# EEG_Front-End.net
KiCad netlist of a schematic drawn in Altium Designer
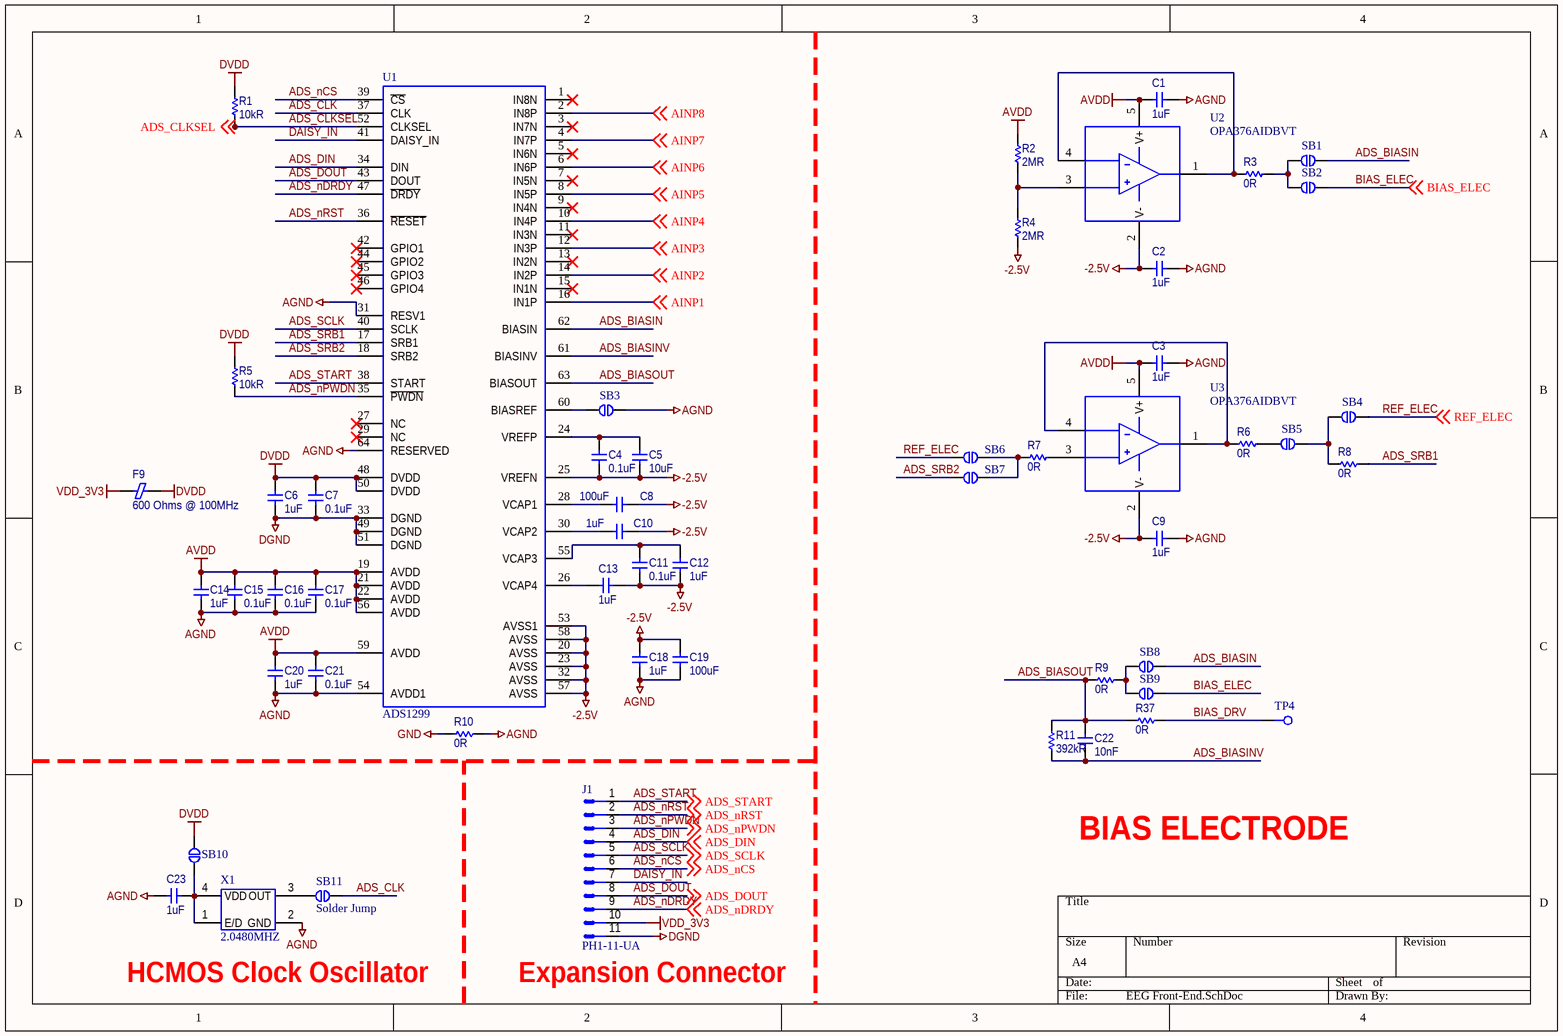
[diagram p0: EEG Front-End.SchDoc]

(export (version "E")
  (design (tool "Eeschema 10.0.6"))
  (components
    (comp (ref "C1")
      (value "1uF")
      (footprint "C1005X04N")
      (description "CAP CER,1UF,10%,16V,X5R,0402,SMD")
      (fields
        (field (name "MANUFACTURER PART NUMBER") "EMK105BJ105KV-F")
        (field (name "MANUFACTURER") "Taiyo Yuden")
      )
      (libsource (lib "Database Library") (part "C_CAPN"))
    )
    (comp (ref "C2")
      (value "1uF")
      (footprint "C1005X04N")
      (description "CAP CER,1UF,10%,16V,X5R,0402,SMD")
      (fields
        (field (name "MANUFACTURER PART NUMBER") "EMK105BJ105KV-F")
        (field (name "MANUFACTURER") "Taiyo Yuden")
      )
      (libsource (lib "Database Library") (part "C_CAPN"))
    )
    (comp (ref "C3")
      (value "1uF")
      (footprint "C1005X04N")
      (description "CAP CER,1UF,10%,16V,X5R,0402,SMD")
      (fields
        (field (name "MANUFACTURER PART NUMBER") "EMK105BJ105KV-F")
        (field (name "MANUFACTURER") "Taiyo Yuden")
      )
      (libsource (lib "Database Library") (part "C_CAPN"))
    )
    (comp (ref "C4")
      (value "0.1uF")
      (footprint "C1005X04N")
      (description "CAP CER,0.1UF,20%,25V,X5R,0402,SMD")
      (fields
        (field (name "MANUFACTURER PART NUMBER") "TMK105BJ104MV-F")
        (field (name "MANUFACTURER") "Taiyo Yuden")
      )
      (libsource (lib "Database Library") (part "C_CAPN"))
    )
    (comp (ref "C5")
      (value "10uF")
      (footprint "C1608X06N")
      (description "CAP CER,10UF,20%,10V,X5R,0603,SMD")
      (fields
        (field (name "MANUFACTURER PART NUMBER") "LMK107BBJ106MAHT")
        (field (name "MANUFACTURER") "Taiyo Yuden")
      )
      (libsource (lib "Database Library") (part "C_CAPN"))
    )
    (comp (ref "C6")
      (value "1uF")
      (footprint "C1005X04N")
      (description "CAP CER,1UF,10%,16V,X5R,0402,SMD")
      (fields
        (field (name "MANUFACTURER PART NUMBER") "EMK105BJ105KV-F")
        (field (name "MANUFACTURER") "Taiyo Yuden")
      )
      (libsource (lib "Database Library") (part "C_CAPN"))
    )
    (comp (ref "C7")
      (value "0.1uF")
      (footprint "C1005X04N")
      (description "CAP CER,0.1UF,20%,25V,X5R,0402,SMD")
      (fields
        (field (name "MANUFACTURER PART NUMBER") "TMK105BJ104MV-F")
        (field (name "MANUFACTURER") "Taiyo Yuden")
      )
      (libsource (lib "Database Library") (part "C_CAPN"))
    )
    (comp (ref "C8")
      (value "100uF")
      (footprint "C2012X06N")
      (description "CAP CER,100UF,20%,6.3V,X5R,0805,SMD")
      (fields
        (field (name "MANUFACTURER PART NUMBER") "GRM21BR60J107ME15L")
        (field (name "MANUFACTURER") "Murata Electronics")
      )
      (libsource (lib "Database Library") (part "C_CAPN"))
    )
    (comp (ref "C9")
      (value "1uF")
      (footprint "C1005X04N")
      (description "CAP CER,1UF,10%,16V,X5R,0402,SMD")
      (fields
        (field (name "MANUFACTURER PART NUMBER") "EMK105BJ105KV-F")
        (field (name "MANUFACTURER") "Taiyo Yuden")
      )
      (libsource (lib "Database Library") (part "C_CAPN"))
    )
    (comp (ref "C10")
      (value "1uF")
      (footprint "C1005X04N")
      (description "CAP CER,1UF,10%,16V,X5R,0402,SMD")
      (fields
        (field (name "MANUFACTURER PART NUMBER") "EMK105BJ105KV-F")
        (field (name "MANUFACTURER") "Taiyo Yuden")
      )
      (libsource (lib "Database Library") (part "C_CAPN"))
    )
    (comp (ref "C11")
      (value "0.1uF")
      (footprint "C1005X04N")
      (description "CAP CER,0.1UF,20%,25V,X5R,0402,SMD")
      (fields
        (field (name "MANUFACTURER PART NUMBER") "TMK105BJ104MV-F")
        (field (name "MANUFACTURER") "Taiyo Yuden")
      )
      (libsource (lib "Database Library") (part "C_CAPN"))
    )
    (comp (ref "C12")
      (value "1uF")
      (footprint "C1005X04N")
      (description "CAP CER,1UF,10%,16V,X5R,0402,SMD")
      (fields
        (field (name "MANUFACTURER PART NUMBER") "EMK105BJ105KV-F")
        (field (name "MANUFACTURER") "Taiyo Yuden")
      )
      (libsource (lib "Database Library") (part "C_CAPN"))
    )
    (comp (ref "C13")
      (value "1uF")
      (footprint "C1005X04N")
      (description "CAP CER,1UF,10%,16V,X5R,0402,SMD")
      (fields
        (field (name "MANUFACTURER PART NUMBER") "EMK105BJ105KV-F")
        (field (name "MANUFACTURER") "Taiyo Yuden")
      )
      (libsource (lib "Database Library") (part "C_CAPN"))
    )
    (comp (ref "C14")
      (value "1uF")
      (footprint "C1005X04N")
      (description "CAP CER,1UF,10%,16V,X5R,0402,SMD")
      (fields
        (field (name "MANUFACTURER PART NUMBER") "EMK105BJ105KV-F")
        (field (name "MANUFACTURER") "Taiyo Yuden")
      )
      (libsource (lib "Database Library") (part "C_CAPN"))
    )
    (comp (ref "C15")
      (value "0.1uF")
      (footprint "C1005X04N")
      (description "CAP CER,0.1UF,20%,25V,X5R,0402,SMD")
      (fields
        (field (name "MANUFACTURER PART NUMBER") "TMK105BJ104MV-F")
        (field (name "MANUFACTURER") "Taiyo Yuden")
      )
      (libsource (lib "Database Library") (part "C_CAPN"))
    )
    (comp (ref "C16")
      (value "0.1uF")
      (footprint "C1005X04N")
      (description "CAP CER,0.1UF,20%,25V,X5R,0402,SMD")
      (fields
        (field (name "MANUFACTURER PART NUMBER") "TMK105BJ104MV-F")
        (field (name "MANUFACTURER") "Taiyo Yuden")
      )
      (libsource (lib "Database Library") (part "C_CAPN"))
    )
    (comp (ref "C17")
      (value "0.1uF")
      (footprint "C1005X04N")
      (description "CAP CER,0.1UF,20%,25V,X5R,0402,SMD")
      (fields
        (field (name "MANUFACTURER PART NUMBER") "TMK105BJ104MV-F")
        (field (name "MANUFACTURER") "Taiyo Yuden")
      )
      (libsource (lib "Database Library") (part "C_CAPN"))
    )
    (comp (ref "C18")
      (value "1uF")
      (footprint "C1005X04N")
      (description "CAP CER,1UF,10%,16V,X5R,0402,SMD")
      (fields
        (field (name "MANUFACTURER PART NUMBER") "EMK105BJ105KV-F")
        (field (name "MANUFACTURER") "Taiyo Yuden")
      )
      (libsource (lib "Database Library") (part "C_CAPN"))
    )
    (comp (ref "C19")
      (value "100uF")
      (footprint "C2012X06N")
      (description "CAP CER,100UF,20%,6.3V,X5R,0805,SMD")
      (fields
        (field (name "MANUFACTURER PART NUMBER") "GRM21BR60J107ME15L")
        (field (name "MANUFACTURER") "Murata Electronics")
      )
      (libsource (lib "Database Library") (part "C_CAPN"))
    )
    (comp (ref "C20")
      (value "1uF")
      (footprint "C1005X04N")
      (description "CAP CER,1UF,10%,16V,X5R,0402,SMD")
      (fields
        (field (name "MANUFACTURER PART NUMBER") "EMK105BJ105KV-F")
        (field (name "MANUFACTURER") "Taiyo Yuden")
      )
      (libsource (lib "Database Library") (part "C_CAPN"))
    )
    (comp (ref "C21")
      (value "0.1uF")
      (footprint "C1005X04N")
      (description "CAP CER,0.1UF,20%,25V,X5R,0402,SMD")
      (fields
        (field (name "MANUFACTURER PART NUMBER") "TMK105BJ104MV-F")
        (field (name "MANUFACTURER") "Taiyo Yuden")
      )
      (libsource (lib "Database Library") (part "C_CAPN"))
    )
    (comp (ref "C22")
      (value "10nF")
      (footprint "C1005X04N")
      (description "CAP CER,10NF,10%,50V,X7R,0402,SMD")
      (fields
        (field (name "MANUFACTURER PART NUMBER") "UMK105B7103KV-F")
        (field (name "MANUFACTURER") "Taiyo Yuden")
      )
      (libsource (lib "Database Library") (part "C_CAPN"))
    )
    (comp (ref "C23")
      (value "1uF")
      (footprint "C1005X04N")
      (description "CAP CER,1UF,10%,16V,X5R,0402,SMD")
      (fields
        (field (name "MANUFACTURER PART NUMBER") "EMK105BJ105KV-F")
        (field (name "MANUFACTURER") "Taiyo Yuden")
      )
      (libsource (lib "Database Library") (part "C_CAPN"))
    )
    (comp (ref "F9")
      (value "600 Ohms @ 100MHz")
      (footprint "F1005X04N")
      (description "FERRITE BEAD,600 OHMS @ 100MHZ,0.55R,300MA,0402,SMD")
      (fields
        (field (name "MANUFACTURER PART NUMBER") "BK1005HS601-T")
        (field (name "MANUFACTURER") "Taiyo Yuden")
      )
      (libsource (lib "Database Library") (part "F_FERRITE_BEAD"))
    )
    (comp (ref "J1")
      (value "PH1-11-UA")
      (footprint "HDR1x11 - 2.54mm")
      (description "CONN HEADER VERT 11POS 2.54MM")
      (libsource (lib "DungMV") (part "PH1-11-UA"))
    )
    (comp (ref "R1")
      (value "10kR")
      (footprint "R1005X04N")
      (description "RES,10KR,1%,62.5MW,0402,SMD")
      (fields
        (field (name "MANUFACTURER PART NUMBER") "RC0402FR-0710KL")
        (field (name "MANUFACTURER") "Yageo")
      )
      (libsource (lib "Database Library") (part "R_RES"))
    )
    (comp (ref "R2")
      (value "2MR")
      (footprint "R1005X04N")
      (description "RES,2MR,1%,62.5MW,0402,SMD")
      (fields
        (field (name "MANUFACTURER PART NUMBER") "CRCW04022M00FKEDC")
        (field (name "MANUFACTURER") "Vishay / Dale")
      )
      (libsource (lib "Database Library") (part "R_RES"))
    )
    (comp (ref "R3")
      (value "0R")
      (footprint "R1005X04N")
      (description "RES,0R,JUMPER,62.5MW,0402,SMD")
      (fields
        (field (name "MANUFACTURER PART NUMBER") "RC0402FR-070RL")
        (field (name "MANUFACTURER") "Yageo")
      )
      (libsource (lib "Database Library") (part "R_RES"))
    )
    (comp (ref "R4")
      (value "2MR")
      (footprint "R1005X04N")
      (description "RES,2MR,1%,62.5MW,0402,SMD")
      (fields
        (field (name "MANUFACTURER PART NUMBER") "CRCW04022M00FKEDC")
        (field (name "MANUFACTURER") "Vishay / Dale")
      )
      (libsource (lib "Database Library") (part "R_RES"))
    )
    (comp (ref "R5")
      (value "10kR")
      (footprint "R1005X04N")
      (description "RES,10KR,1%,62.5MW,0402,SMD")
      (fields
        (field (name "MANUFACTURER PART NUMBER") "RC0402FR-0710KL")
        (field (name "MANUFACTURER") "Yageo")
      )
      (libsource (lib "Database Library") (part "R_RES"))
    )
    (comp (ref "R6")
      (value "0R")
      (footprint "R1005X04N")
      (description "RES,0R,JUMPER,62.5MW,0402,SMD")
      (fields
        (field (name "MANUFACTURER PART NUMBER") "RC0402FR-070RL")
        (field (name "MANUFACTURER") "Yageo")
      )
      (libsource (lib "Database Library") (part "R_RES"))
    )
    (comp (ref "R7")
      (value "0R")
      (footprint "R1005X04N")
      (description "RES,0R,JUMPER,62.5MW,0402,SMD")
      (fields
        (field (name "MANUFACTURER PART NUMBER") "RC0402FR-070RL")
        (field (name "MANUFACTURER") "Yageo")
      )
      (libsource (lib "Database Library") (part "R_RES"))
    )
    (comp (ref "R8")
      (value "0R")
      (footprint "R1005X04N")
      (description "RES,0R,JUMPER,62.5MW,0402,SMD")
      (fields
        (field (name "MANUFACTURER PART NUMBER") "RC0402FR-070RL")
        (field (name "MANUFACTURER") "Yageo")
      )
      (libsource (lib "Database Library") (part "R_RES"))
    )
    (comp (ref "R9")
      (value "0R")
      (footprint "R1005X04N")
      (description "RES,0R,JUMPER,62.5MW,0402,SMD")
      (fields
        (field (name "MANUFACTURER PART NUMBER") "RC0402FR-070RL")
        (field (name "MANUFACTURER") "Yageo")
      )
      (libsource (lib "Database Library") (part "R_RES"))
    )
    (comp (ref "R10")
      (value "0R")
      (footprint "R1005X04N")
      (description "RES,0R,JUMPER,62.5MW,0402,SMD")
      (fields
        (field (name "MANUFACTURER PART NUMBER") "RC0402FR-070RL")
        (field (name "MANUFACTURER") "Yageo")
      )
      (libsource (lib "Database Library") (part "R_RES"))
    )
    (comp (ref "R11")
      (value "392kR")
      (footprint "R1005X04N")
      (description "RES,392KR,1%,62.5MW,0402,SMD")
      (fields
        (field (name "MANUFACTURER PART NUMBER") "CRCW0402392KFKED")
        (field (name "MANUFACTURER") "Vishay / Dale")
      )
      (libsource (lib "Database Library") (part "R_RES"))
    )
    (comp (ref "R37")
      (value "0R")
      (footprint "R1005X04N")
      (description "RES,0R,JUMPER,62.5MW,0402,SMD")
      (fields
        (field (name "MANUFACTURER PART NUMBER") "RC0402FR-070RL")
        (field (name "MANUFACTURER") "Yageo")
      )
      (libsource (lib "Database Library") (part "R_RES"))
    )
    (comp (ref "SB1")
      (value "Solder Jump")
      (footprint "SJB_0603")
      (description "Solder Bridge Jumper 0603")
      (libsource (lib "DungMV") (part "Solder Jump"))
    )
    (comp (ref "SB2")
      (value "Solder Jump")
      (footprint "SJB_0603")
      (description "Solder Bridge Jumper 0603")
      (libsource (lib "DungMV") (part "Solder Jump"))
    )
    (comp (ref "SB3")
      (value "Solder Jump")
      (footprint "SJB_0603")
      (description "Solder Bridge Jumper 0603")
      (libsource (lib "DungMV") (part "Solder Jump"))
    )
    (comp (ref "SB4")
      (value "Solder Jump")
      (footprint "SJB_0603")
      (description "Solder Bridge Jumper 0603")
      (libsource (lib "DungMV") (part "Solder Jump"))
    )
    (comp (ref "SB5")
      (value "Solder Jump")
      (footprint "SJB_0603")
      (description "Solder Bridge Jumper 0603")
      (libsource (lib "DungMV") (part "Solder Jump"))
    )
    (comp (ref "SB6")
      (value "Solder Jump")
      (footprint "SJB_0603")
      (description "Solder Bridge Jumper 0603")
      (libsource (lib "DungMV") (part "Solder Jump"))
    )
    (comp (ref "SB7")
      (value "Solder Jump")
      (footprint "SJB_0603")
      (description "Solder Bridge Jumper 0603")
      (libsource (lib "DungMV") (part "Solder Jump"))
    )
    (comp (ref "SB8")
      (value "Solder Jump")
      (footprint "SJB_0603")
      (description "Solder Bridge Jumper 0603")
      (libsource (lib "DungMV") (part "Solder Jump"))
    )
    (comp (ref "SB9")
      (value "Solder Jump")
      (footprint "SJB_0603")
      (description "Solder Bridge Jumper 0603")
      (libsource (lib "DungMV") (part "Solder Jump"))
    )
    (comp (ref "SB10")
      (value "Solder Jump")
      (footprint "SJB_0603")
      (description "Solder Bridge Jumper 0603")
      (libsource (lib "DungMV") (part "Solder Jump"))
    )
    (comp (ref "SB11")
      (value "Solder Jump")
      (footprint "SJB_0603")
      (description "Solder Bridge Jumper 0603")
      (libsource (lib "DungMV") (part "Solder Jump"))
    )
    (comp (ref "TP4")
      (value "TP_25MILC")
      (footprint "TESTPOINT_1MM")
      (description "Test Point 25mil")
      (libsource (lib "DungMV") (part "TP_25MILC"))
    )
    (comp (ref "U1")
      (value "ADS1299")
      (footprint "PQFN-64")
      (description "IC AFE 8 CHAN 24BIT 64TQFP")
      (fields
        (field (name "MANUFACTURER") "Texas Instruments")
        (field (name "MANUFACTURER PART NUMBER") "ADS1299IPAGR")
      )
      (libsource (lib "DungMV") (part "ADS1299IPAGR"))
    )
    (comp (ref "U2")
      (value "OPA376AIDBVT")
      (footprint "SOT23-5")
      (description "IC OPAMP GP 1 CIRCUIT SOT23-5")
      (fields (field (name "MANUFACTURER") "Texas Instruments"))
      (libsource (lib "DungMV") (part "OPA376AIDBVT"))
    )
    (comp (ref "U3")
      (value "OPA376AIDBVT")
      (footprint "SOT23-5")
      (description "IC OPAMP GP 1 CIRCUIT SOT23-5")
      (fields (field (name "MANUFACTURER") "Texas Instruments"))
      (libsource (lib "DungMV") (part "OPA376AIDBVT"))
    )
    (comp (ref "X1")
      (value "2.0480MHZ")
      (footprint "CRYSTAL_3225")
      (description "XTAL OSC XO 2.0480MHZ HCMOS SMD")
      (fields (field (name "MANUFACTURER") "CTS-Frequency Controls"))
      (libsource (lib "DungMV") (part "632L3I002M04800"))
    )
  )
  (nets
    (net (code "1") (name "-2.5V") (class "Default")
      (node (ref "C10") (pin "2") (pinfunction "2_2") (pintype "passive"))
      (node (ref "C11") (pin "1") (pinfunction "1_1") (pintype "passive"))
      (node (ref "C12") (pin "2") (pinfunction "2_2") (pintype "passive"))
      (node (ref "C13") (pin "1") (pinfunction "1_1") (pintype "passive"))
      (node (ref "C18") (pin "2") (pinfunction "2_2") (pintype "passive"))
      (node (ref "C19") (pin "2") (pinfunction "2_2") (pintype "passive"))
      (node (ref "C2") (pin "2") (pinfunction "2_2") (pintype "passive"))
      (node (ref "C4") (pin "1") (pinfunction "1_1") (pintype "passive"))
      (node (ref "C5") (pin "1") (pinfunction "1_1") (pintype "passive"))
      (node (ref "C8") (pin "2") (pinfunction "2_2") (pintype "passive"))
      (node (ref "C9") (pin "2") (pinfunction "2_2") (pintype "passive"))
      (node (ref "R4") (pin "1") (pinfunction "1_1") (pintype "passive"))
      (node (ref "U1") (pin "20") (pinfunction "AVSS_20") (pintype "passive"))
      (node (ref "U1") (pin "23") (pinfunction "AVSS_23") (pintype "passive"))
      (node (ref "U1") (pin "25") (pinfunction "VREFN_25") (pintype "passive"))
      (node (ref "U1") (pin "32") (pinfunction "AVSS_32") (pintype "passive"))
      (node (ref "U1") (pin "53") (pinfunction "AVSS1_53") (pintype "passive"))
      (node (ref "U1") (pin "57") (pinfunction "AVSS_57") (pintype "passive"))
      (node (ref "U1") (pin "58") (pinfunction "AVSS_58") (pintype "passive"))
      (node (ref "U2") (pin "2") (pinfunction "V-_2") (pintype "power_in"))
      (node (ref "U3") (pin "2") (pinfunction "V-_2") (pintype "power_in"))
    )
    (net (code "2") (name "/ADS_BIASIN") (class "Default")
      (node (ref "SB1") (pin "1") (pinfunction "1_1") (pintype "passive"))
      (node (ref "SB8") (pin "1") (pinfunction "1_1") (pintype "passive"))
      (node (ref "U1") (pin "62") (pinfunction "BIASIN_62") (pintype "passive"))
    )
    (net (code "3") (name "/ADS_BIASINV") (class "Default")
      (node (ref "C22") (pin "1") (pinfunction "1_1") (pintype "passive"))
      (node (ref "R11") (pin "1") (pinfunction "1_1") (pintype "passive"))
      (node (ref "U1") (pin "61") (pinfunction "BIASINV_61") (pintype "passive"))
    )
    (net (code "4") (name "/ADS_BIASOUT") (class "Default")
      (node (ref "C22") (pin "2") (pinfunction "2_2") (pintype "passive"))
      (node (ref "R11") (pin "2") (pinfunction "2_2") (pintype "passive"))
      (node (ref "R37") (pin "1") (pinfunction "1_1") (pintype "passive"))
      (node (ref "R9") (pin "1") (pinfunction "1_1") (pintype "passive"))
      (node (ref "U1") (pin "63") (pinfunction "BIASOUT_63") (pintype "passive"))
    )
    (net (code "5") (name "/ADS_CLK") (class "Default")
      (node (ref "SB11") (pin "2") (pinfunction "2_2") (pintype "passive"))
      (node (ref "U1") (pin "37") (pinfunction "CLK_37") (pintype "passive"))
    )
    (net (code "6") (name "/ADS_SRB1") (class "Default")
      (node (ref "R8") (pin "2") (pinfunction "2_2") (pintype "passive"))
      (node (ref "U1") (pin "17") (pinfunction "SRB1_17") (pintype "passive"))
    )
    (net (code "7") (name "/ADS_SRB2") (class "Default")
      (node (ref "SB7") (pin "2") (pinfunction "2_2") (pintype "passive"))
      (node (ref "U1") (pin "18") (pinfunction "SRB2_18") (pintype "passive"))
    )
    (net (code "8") (name "/BIAS_DRV") (class "Default")
      (node (ref "R37") (pin "2") (pinfunction "2_2") (pintype "passive"))
      (node (ref "TP4") (pin "1") (pinfunction "1_1") (pintype "passive"))
    )
    (net (code "9") (name "/DAISY_IN") (class "Default")
      (node (ref "J1") (pin "7") (pinfunction "7_7") (pintype "passive"))
      (node (ref "U1") (pin "41") (pinfunction "DAISY_IN_41") (pintype "passive"))
    )
    (net (code "10") (name "ADS_CLKSEL") (class "Default")
      (node (ref "R1") (pin "1") (pinfunction "1_1") (pintype "passive"))
      (node (ref "U1") (pin "52") (pinfunction "CLKSEL_52") (pintype "passive"))
    )
    (net (code "11") (name "ADS_DIN") (class "Default")
      (node (ref "J1") (pin "4") (pinfunction "4_4") (pintype "passive"))
      (node (ref "U1") (pin "34") (pinfunction "DIN_34") (pintype "passive"))
    )
    (net (code "12") (name "ADS_DOUT") (class "Default")
      (node (ref "J1") (pin "8") (pinfunction "8_8") (pintype "passive"))
      (node (ref "U1") (pin "43") (pinfunction "DOUT_43") (pintype "passive"))
    )
    (net (code "13") (name "ADS_SCLK") (class "Default")
      (node (ref "J1") (pin "5") (pinfunction "5_5") (pintype "passive"))
      (node (ref "U1") (pin "40") (pinfunction "SCLK_40") (pintype "passive"))
    )
    (net (code "14") (name "ADS_START") (class "Default")
      (node (ref "J1") (pin "1") (pinfunction "1_1") (pintype "passive"))
      (node (ref "U1") (pin "38") (pinfunction "START_38") (pintype "passive"))
    )
    (net (code "15") (name "ADS_nCS") (class "Default")
      (node (ref "J1") (pin "6") (pinfunction "6_6") (pintype "passive"))
      (node (ref "U1") (pin "39") (pinfunction "~{CS}_39") (pintype "passive"))
    )
    (net (code "16") (name "ADS_nDRDY") (class "Default")
      (node (ref "J1") (pin "9") (pinfunction "9_9") (pintype "passive"))
      (node (ref "U1") (pin "47") (pinfunction "~{DRDY}_47") (pintype "passive"))
    )
    (net (code "17") (name "ADS_nPWDN") (class "Default")
      (node (ref "J1") (pin "3") (pinfunction "3_3") (pintype "passive"))
      (node (ref "R5") (pin "1") (pinfunction "1_1") (pintype "passive"))
      (node (ref "U1") (pin "35") (pinfunction "~{PWDN}_35") (pintype "passive"))
    )
    (net (code "18") (name "ADS_nRST") (class "Default")
      (node (ref "J1") (pin "2") (pinfunction "2_2") (pintype "passive"))
      (node (ref "U1") (pin "36") (pinfunction "~{RESET}_36") (pintype "passive"))
    )
    (net (code "19") (name "AGND") (class "Default")
      (node (ref "C1") (pin "1") (pinfunction "1_1") (pintype "passive"))
      (node (ref "C14") (pin "2") (pinfunction "2_2") (pintype "passive"))
      (node (ref "C15") (pin "1") (pinfunction "1_1") (pintype "passive"))
      (node (ref "C16") (pin "1") (pinfunction "1_1") (pintype "passive"))
      (node (ref "C17") (pin "1") (pinfunction "1_1") (pintype "passive"))
      (node (ref "C18") (pin "1") (pinfunction "1_1") (pintype "passive"))
      (node (ref "C19") (pin "1") (pinfunction "1_1") (pintype "passive"))
      (node (ref "C2") (pin "1") (pinfunction "1_1") (pintype "passive"))
      (node (ref "C20") (pin "2") (pinfunction "2_2") (pintype "passive"))
      (node (ref "C21") (pin "1") (pinfunction "1_1") (pintype "passive"))
      (node (ref "C23") (pin "1") (pinfunction "1_1") (pintype "passive"))
      (node (ref "C3") (pin "1") (pinfunction "1_1") (pintype "passive"))
      (node (ref "C9") (pin "1") (pinfunction "1_1") (pintype "passive"))
      (node (ref "R10") (pin "2") (pinfunction "2_2") (pintype "passive"))
      (node (ref "SB3") (pin "1") (pinfunction "1_1") (pintype "passive"))
      (node (ref "U1") (pin "31") (pinfunction "RESV1_31") (pintype "passive"))
      (node (ref "U1") (pin "54") (pinfunction "AVDD1_54") (pintype "passive"))
      (node (ref "U1") (pin "64") (pinfunction "RESERVED_64") (pintype "passive"))
      (node (ref "X1") (pin "2") (pinfunction "GND_2") (pintype "passive"))
    )
    (net (code "20") (name "AINP1") (class "Default")
      (node (ref "U1") (pin "16") (pinfunction "IN1P_16") (pintype "passive"))
    )
    (net (code "21") (name "AINP2") (class "Default")
      (node (ref "U1") (pin "14") (pinfunction "IN2P_14") (pintype "passive"))
    )
    (net (code "22") (name "AINP3") (class "Default")
      (node (ref "U1") (pin "12") (pinfunction "IN3P_12") (pintype "passive"))
    )
    (net (code "23") (name "AINP4") (class "Default")
      (node (ref "U1") (pin "10") (pinfunction "IN4P_10") (pintype "passive"))
    )
    (net (code "24") (name "AINP5") (class "Default")
      (node (ref "U1") (pin "8") (pinfunction "IN5P_8") (pintype "passive"))
    )
    (net (code "25") (name "AINP6") (class "Default")
      (node (ref "U1") (pin "6") (pinfunction "IN6P_6") (pintype "passive"))
    )
    (net (code "26") (name "AINP7") (class "Default")
      (node (ref "U1") (pin "4") (pinfunction "IN7P_4") (pintype "passive"))
    )
    (net (code "27") (name "AINP8") (class "Default")
      (node (ref "U1") (pin "2") (pinfunction "IN8P_2") (pintype "passive"))
    )
    (net (code "28") (name "AVDD") (class "Default")
      (node (ref "C1") (pin "2") (pinfunction "2_2") (pintype "passive"))
      (node (ref "C14") (pin "1") (pinfunction "1_1") (pintype "passive"))
      (node (ref "C15") (pin "2") (pinfunction "2_2") (pintype "passive"))
      (node (ref "C16") (pin "2") (pinfunction "2_2") (pintype "passive"))
      (node (ref "C17") (pin "2") (pinfunction "2_2") (pintype "passive"))
      (node (ref "C20") (pin "1") (pinfunction "1_1") (pintype "passive"))
      (node (ref "C21") (pin "2") (pinfunction "2_2") (pintype "passive"))
      (node (ref "C3") (pin "2") (pinfunction "2_2") (pintype "passive"))
      (node (ref "R2") (pin "2") (pinfunction "2_2") (pintype "passive"))
      (node (ref "U1") (pin "19") (pinfunction "AVDD_19") (pintype "passive"))
      (node (ref "U1") (pin "21") (pinfunction "AVDD_21") (pintype "passive"))
      (node (ref "U1") (pin "22") (pinfunction "AVDD_22") (pintype "passive"))
      (node (ref "U1") (pin "56") (pinfunction "AVDD_56") (pintype "passive"))
      (node (ref "U1") (pin "59") (pinfunction "AVDD_59") (pintype "passive"))
      (node (ref "U2") (pin "5") (pinfunction "V+_5") (pintype "power_in"))
      (node (ref "U3") (pin "5") (pinfunction "V+_5") (pintype "power_in"))
    )
    (net (code "29") (name "BIAS_ELEC") (class "Default")
      (node (ref "SB2") (pin "1") (pinfunction "1_1") (pintype "passive"))
      (node (ref "SB9") (pin "1") (pinfunction "1_1") (pintype "passive"))
    )
    (net (code "30") (name "DGND") (class "Default")
      (node (ref "C6") (pin "2") (pinfunction "2_2") (pintype "passive"))
      (node (ref "C7") (pin "1") (pinfunction "1_1") (pintype "passive"))
      (node (ref "J1") (pin "11") (pinfunction "11_11") (pintype "passive"))
      (node (ref "U1") (pin "33") (pinfunction "DGND_33") (pintype "passive"))
      (node (ref "U1") (pin "49") (pinfunction "DGND_49") (pintype "passive"))
      (node (ref "U1") (pin "51") (pinfunction "DGND_51") (pintype "passive"))
    )
    (net (code "31") (name "DVDD") (class "Default")
      (node (ref "C6") (pin "1") (pinfunction "1_1") (pintype "passive"))
      (node (ref "C7") (pin "2") (pinfunction "2_2") (pintype "passive"))
      (node (ref "F9") (pin "2") (pinfunction "2_2") (pintype "passive"))
      (node (ref "R1") (pin "2") (pinfunction "2_2") (pintype "passive"))
      (node (ref "R5") (pin "2") (pinfunction "2_2") (pintype "passive"))
      (node (ref "SB10") (pin "1") (pinfunction "1_1") (pintype "passive"))
      (node (ref "U1") (pin "48") (pinfunction "DVDD_48") (pintype "passive"))
      (node (ref "U1") (pin "50") (pinfunction "DVDD_50") (pintype "passive"))
    )
    (net (code "32") (name "GND") (class "Default")
      (node (ref "R10") (pin "1") (pinfunction "1_1") (pintype "passive"))
    )
    (net (code "33") (name "Net-(R3-Pad2)") (class "Default")
      (node (ref "R3") (pin "2") (pinfunction "2_2") (pintype "passive"))
      (node (ref "SB1") (pin "2") (pinfunction "2_2") (pintype "passive"))
      (node (ref "SB2") (pin "2") (pinfunction "2_2") (pintype "passive"))
    )
    (net (code "34") (name "Net-(R6-Pad2)") (class "Default")
      (node (ref "R6") (pin "2") (pinfunction "2_2") (pintype "passive"))
      (node (ref "SB5") (pin "2") (pinfunction "2_2") (pintype "passive"))
    )
    (net (code "35") (name "Net-(R7-Pad1)") (class "Default")
      (node (ref "R7") (pin "1") (pinfunction "1_1") (pintype "passive"))
      (node (ref "SB6") (pin "1") (pinfunction "1_1") (pintype "passive"))
      (node (ref "SB7") (pin "1") (pinfunction "1_1") (pintype "passive"))
    )
    (net (code "36") (name "Net-(R8-Pad1)") (class "Default")
      (node (ref "R8") (pin "1") (pinfunction "1_1") (pintype "passive"))
      (node (ref "SB4") (pin "1") (pinfunction "1_1") (pintype "passive"))
      (node (ref "SB5") (pin "1") (pinfunction "1_1") (pintype "passive"))
    )
    (net (code "37") (name "Net-(R9-Pad2)") (class "Default")
      (node (ref "R9") (pin "2") (pinfunction "2_2") (pintype "passive"))
      (node (ref "SB8") (pin "2") (pinfunction "2_2") (pintype "passive"))
      (node (ref "SB9") (pin "2") (pinfunction "2_2") (pintype "passive"))
    )
    (net (code "38") (name "Net-(U1-BIASREF)") (class "Default")
      (node (ref "SB3") (pin "2") (pinfunction "2_2") (pintype "passive"))
      (node (ref "U1") (pin "60") (pinfunction "BIASREF_60") (pintype "passive"))
    )
    (net (code "39") (name "Net-(U1-VCAP1)") (class "Default")
      (node (ref "C8") (pin "1") (pinfunction "1_1") (pintype "passive"))
      (node (ref "U1") (pin "28") (pinfunction "VCAP1_28") (pintype "passive"))
    )
    (net (code "40") (name "Net-(U1-VCAP2)") (class "Default")
      (node (ref "C10") (pin "1") (pinfunction "1_1") (pintype "passive"))
      (node (ref "U1") (pin "30") (pinfunction "VCAP2_30") (pintype "passive"))
    )
    (net (code "41") (name "Net-(U1-VCAP3)") (class "Default")
      (node (ref "C11") (pin "2") (pinfunction "2_2") (pintype "passive"))
      (node (ref "C12") (pin "1") (pinfunction "1_1") (pintype "passive"))
      (node (ref "U1") (pin "55") (pinfunction "VCAP3_55") (pintype "passive"))
    )
    (net (code "42") (name "Net-(U1-VCAP4)") (class "Default")
      (node (ref "C13") (pin "2") (pinfunction "2_2") (pintype "passive"))
      (node (ref "U1") (pin "26") (pinfunction "VCAP4_26") (pintype "passive"))
    )
    (net (code "43") (name "Net-(U1-VREFP)") (class "Default")
      (node (ref "C4") (pin "2") (pinfunction "2_2") (pintype "passive"))
      (node (ref "C5") (pin "2") (pinfunction "2_2") (pintype "passive"))
      (node (ref "U1") (pin "24") (pinfunction "VREFP_24") (pintype "passive"))
    )
    (net (code "44") (name "Net-(U2-IN+)") (class "Default")
      (node (ref "R2") (pin "1") (pinfunction "1_1") (pintype "passive"))
      (node (ref "R4") (pin "2") (pinfunction "2_2") (pintype "passive"))
      (node (ref "U2") (pin "3") (pinfunction "IN+_3") (pintype "passive"))
    )
    (net (code "45") (name "Net-(U2-IN-)") (class "Default")
      (node (ref "R3") (pin "1") (pinfunction "1_1") (pintype "passive"))
      (node (ref "U2") (pin "1") (pinfunction "VO_1") (pintype "passive"))
      (node (ref "U2") (pin "4") (pinfunction "IN-_4") (pintype "passive"))
    )
    (net (code "46") (name "Net-(U3-IN+)") (class "Default")
      (node (ref "R7") (pin "2") (pinfunction "2_2") (pintype "passive"))
      (node (ref "U3") (pin "3") (pinfunction "IN+_3") (pintype "passive"))
    )
    (net (code "47") (name "Net-(U3-IN-)") (class "Default")
      (node (ref "R6") (pin "1") (pinfunction "1_1") (pintype "passive"))
      (node (ref "U3") (pin "1") (pinfunction "VO_1") (pintype "passive"))
      (node (ref "U3") (pin "4") (pinfunction "IN-_4") (pintype "passive"))
    )
    (net (code "48") (name "Net-(X1-E{slash}D)") (class "Default")
      (node (ref "C23") (pin "2") (pinfunction "2_2") (pintype "passive"))
      (node (ref "SB10") (pin "2") (pinfunction "2_2") (pintype "passive"))
      (node (ref "X1") (pin "1") (pinfunction "E/D_1") (pintype "passive"))
      (node (ref "X1") (pin "4") (pinfunction "VDD_4") (pintype "passive"))
    )
    (net (code "49") (name "Net-(X1-OUT)") (class "Default")
      (node (ref "SB11") (pin "1") (pinfunction "1_1") (pintype "passive"))
      (node (ref "X1") (pin "3") (pinfunction "OUT_3") (pintype "passive"))
    )
    (net (code "50") (name "REF_ELEC") (class "Default")
      (node (ref "SB4") (pin "2") (pinfunction "2_2") (pintype "passive"))
      (node (ref "SB6") (pin "2") (pinfunction "2_2") (pintype "passive"))
    )
    (net (code "51") (name "VDD_3V3") (class "Default")
      (node (ref "F9") (pin "1") (pinfunction "1_1") (pintype "passive"))
      (node (ref "J1") (pin "10") (pinfunction "10_10") (pintype "passive"))
    )
    (net (code "52") (name "unconnected-(U1-GPIO1-Pad42)") (class "Default")
      (node (ref "U1") (pin "42") (pinfunction "GPIO1_42") (pintype "passive+no_connect"))
    )
    (net (code "53") (name "unconnected-(U1-GPIO2-Pad44)") (class "Default")
      (node (ref "U1") (pin "44") (pinfunction "GPIO2_44") (pintype "passive+no_connect"))
    )
    (net (code "54") (name "unconnected-(U1-GPIO3-Pad45)") (class "Default")
      (node (ref "U1") (pin "45") (pinfunction "GPIO3_45") (pintype "passive+no_connect"))
    )
    (net (code "55") (name "unconnected-(U1-GPIO4-Pad46)") (class "Default")
      (node (ref "U1") (pin "46") (pinfunction "GPIO4_46") (pintype "passive+no_connect"))
    )
    (net (code "56") (name "unconnected-(U1-IN1N-Pad15)") (class "Default")
      (node (ref "U1") (pin "15") (pinfunction "IN1N_15") (pintype "passive+no_connect"))
    )
    (net (code "57") (name "unconnected-(U1-IN2N-Pad13)") (class "Default")
      (node (ref "U1") (pin "13") (pinfunction "IN2N_13") (pintype "passive+no_connect"))
    )
    (net (code "58") (name "unconnected-(U1-IN3N-Pad11)") (class "Default")
      (node (ref "U1") (pin "11") (pinfunction "IN3N_11") (pintype "passive+no_connect"))
    )
    (net (code "59") (name "unconnected-(U1-IN4N-Pad9)") (class "Default")
      (node (ref "U1") (pin "9") (pinfunction "IN4N_9") (pintype "passive+no_connect"))
    )
    (net (code "60") (name "unconnected-(U1-IN5N-Pad7)") (class "Default")
      (node (ref "U1") (pin "7") (pinfunction "IN5N_7") (pintype "passive+no_connect"))
    )
    (net (code "61") (name "unconnected-(U1-IN6N-Pad5)") (class "Default")
      (node (ref "U1") (pin "5") (pinfunction "IN6N_5") (pintype "passive+no_connect"))
    )
    (net (code "62") (name "unconnected-(U1-IN7N-Pad3)") (class "Default")
      (node (ref "U1") (pin "3") (pinfunction "IN7N_3") (pintype "passive+no_connect"))
    )
    (net (code "63") (name "unconnected-(U1-IN8N-Pad1)") (class "Default")
      (node (ref "U1") (pin "1") (pinfunction "IN8N_1") (pintype "passive+no_connect"))
    )
    (net (code "64") (name "unconnected-(U1-NC-Pad27)") (class "Default")
      (node (ref "U1") (pin "27") (pinfunction "NC_27") (pintype "passive+no_connect"))
    )
    (net (code "65") (name "unconnected-(U1-NC-Pad29)") (class "Default")
      (node (ref "U1") (pin "29") (pinfunction "NC_29") (pintype "passive+no_connect"))
    )
  )
)
